# Sensor_board.net
KiCad netlist of a schematic drawn in EAGLE
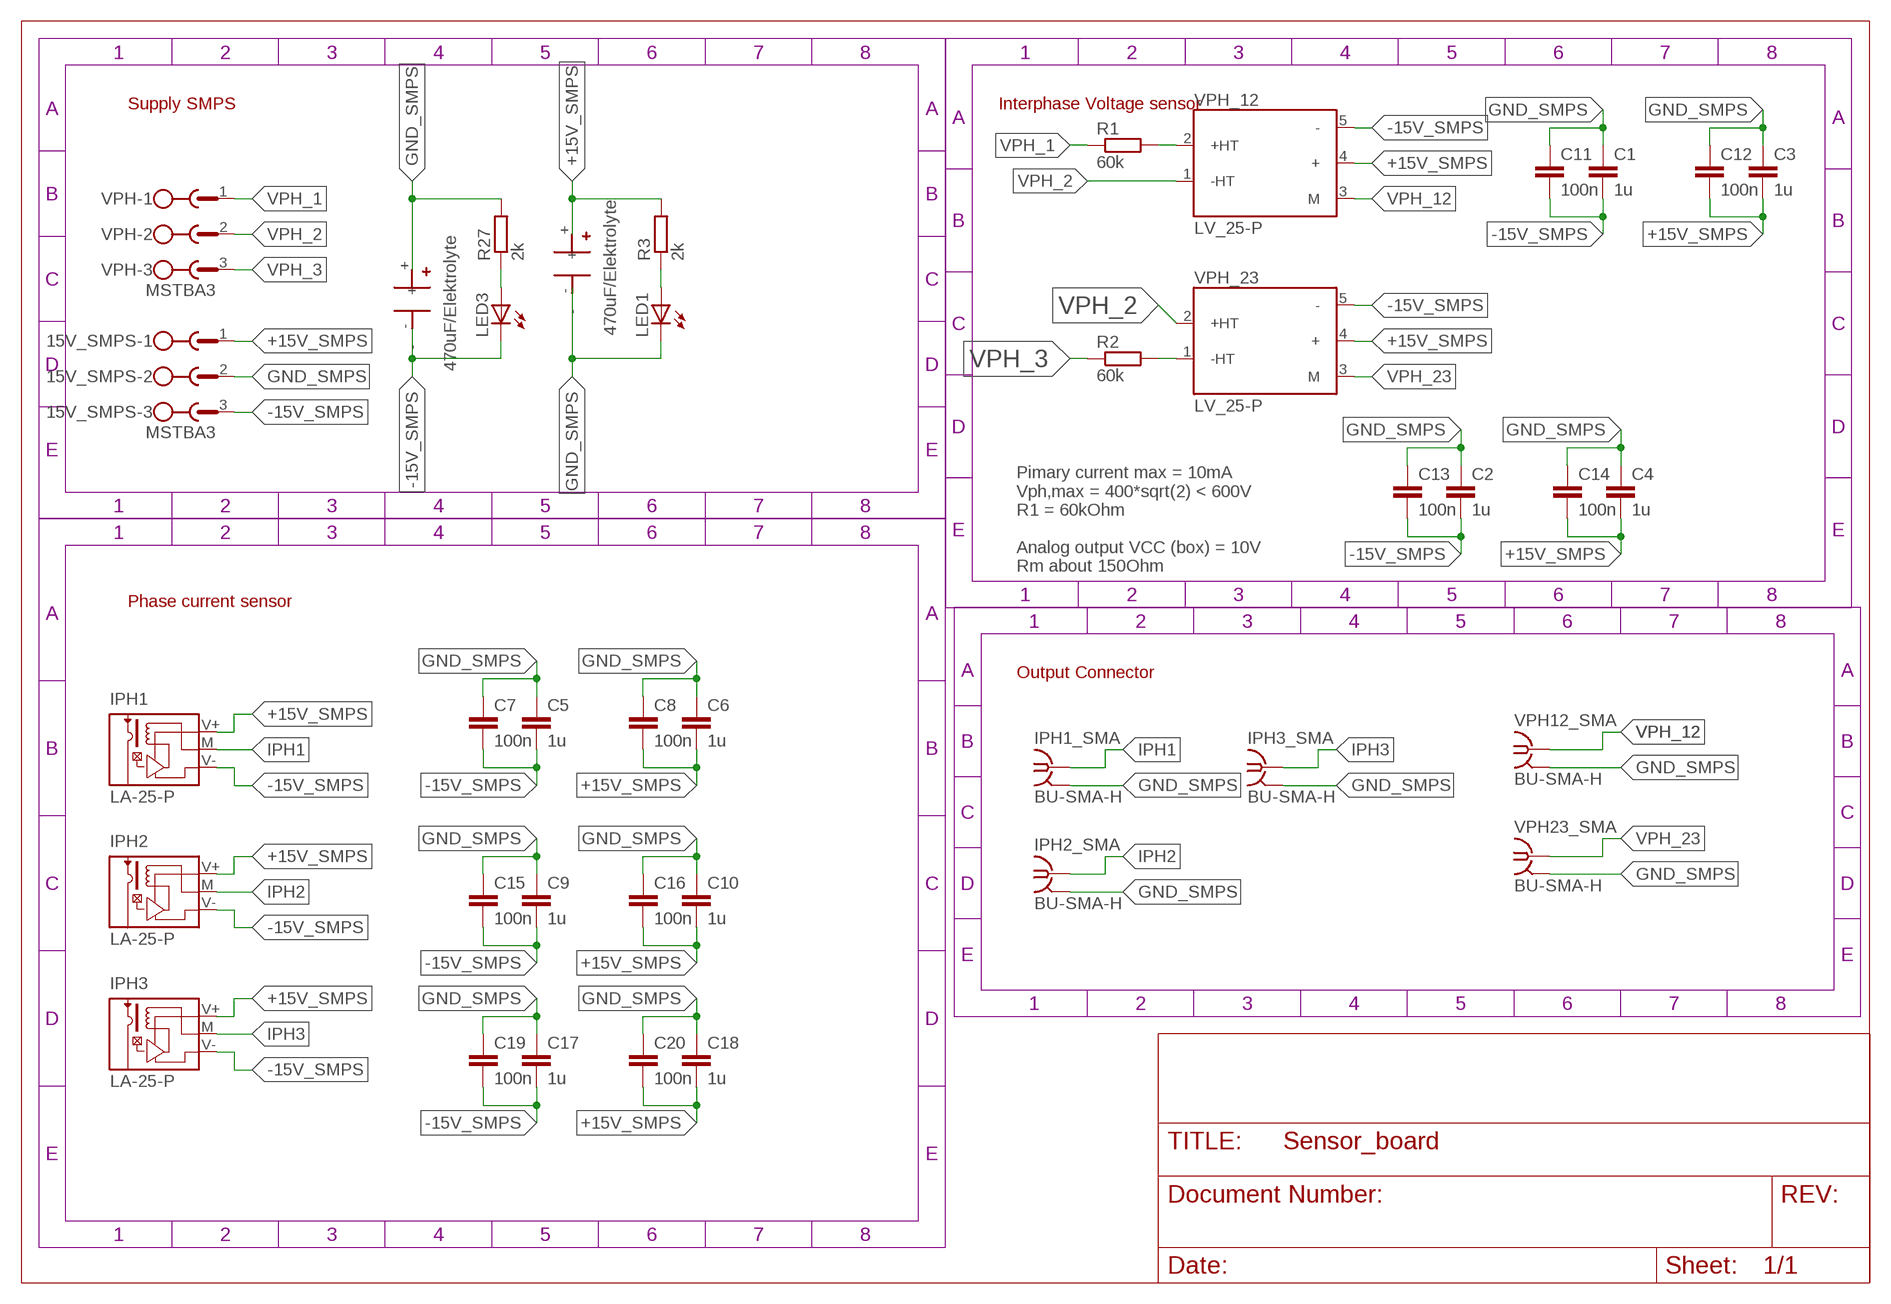
[diagram p0: schematic, sheet 1]

(export (version "E")
  (design (tool "Eeschema 10.0.6"))
  (components
    (comp (ref "15V_SMPS")
      (value "MSTBA3")
      (footprint "eagle-import:MSTBA3")
      (fields (field (name "MF") "FARNELL") (field (name "MPN") "1757255"))
      (libsource (lib "eagle-import") (part "MSTBA3"))
    )
    (comp (ref "C1")
      (value "1u")
      (footprint "eagle-import:C0805")
      (libsource (lib "eagle-import") (part "C-EUC0805"))
    )
    (comp (ref "C2")
      (value "1u")
      (footprint "eagle-import:C0805")
      (libsource (lib "eagle-import") (part "C-EUC0805"))
    )
    (comp (ref "C3")
      (value "1u")
      (footprint "eagle-import:C0805")
      (libsource (lib "eagle-import") (part "C-EUC0805"))
    )
    (comp (ref "C4")
      (value "1u")
      (footprint "eagle-import:C0805")
      (libsource (lib "eagle-import") (part "C-EUC0805"))
    )
    (comp (ref "C5")
      (value "1u")
      (footprint "eagle-import:C0805")
      (libsource (lib "eagle-import") (part "C-EUC0805"))
    )
    (comp (ref "C6")
      (value "1u")
      (footprint "eagle-import:C0805")
      (libsource (lib "eagle-import") (part "C-EUC0805"))
    )
    (comp (ref "C7")
      (value "100n")
      (footprint "eagle-import:C0805")
      (libsource (lib "eagle-import") (part "C-EUC0805"))
    )
    (comp (ref "C8")
      (value "100n")
      (footprint "eagle-import:C0805")
      (libsource (lib "eagle-import") (part "C-EUC0805"))
    )
    (comp (ref "C9")
      (value "1u")
      (footprint "eagle-import:C0805")
      (libsource (lib "eagle-import") (part "C-EUC0805"))
    )
    (comp (ref "C10")
      (value "1u")
      (footprint "eagle-import:C0805")
      (libsource (lib "eagle-import") (part "C-EUC0805"))
    )
    (comp (ref "C11")
      (value "100n")
      (footprint "eagle-import:C0805")
      (libsource (lib "eagle-import") (part "C-EUC0805"))
    )
    (comp (ref "C12")
      (value "100n")
      (footprint "eagle-import:C0805")
      (libsource (lib "eagle-import") (part "C-EUC0805"))
    )
    (comp (ref "C13")
      (value "100n")
      (footprint "eagle-import:C0805")
      (libsource (lib "eagle-import") (part "C-EUC0805"))
    )
    (comp (ref "C14")
      (value "100n")
      (footprint "eagle-import:C0805")
      (libsource (lib "eagle-import") (part "C-EUC0805"))
    )
    (comp (ref "C15")
      (value "100n")
      (footprint "eagle-import:C0805")
      (libsource (lib "eagle-import") (part "C-EUC0805"))
    )
    (comp (ref "C16")
      (value "100n")
      (footprint "eagle-import:C0805")
      (libsource (lib "eagle-import") (part "C-EUC0805"))
    )
    (comp (ref "C17")
      (value "1u")
      (footprint "eagle-import:C0805")
      (libsource (lib "eagle-import") (part "C-EUC0805"))
    )
    (comp (ref "C18")
      (value "1u")
      (footprint "eagle-import:C0805")
      (libsource (lib "eagle-import") (part "C-EUC0805"))
    )
    (comp (ref "C19")
      (value "100n")
      (footprint "eagle-import:C0805")
      (libsource (lib "eagle-import") (part "C-EUC0805"))
    )
    (comp (ref "C20")
      (value "100n")
      (footprint "eagle-import:C0805")
      (libsource (lib "eagle-import") (part "C-EUC0805"))
    )
    (comp (ref "IPH1")
      (value "LA-25-P")
      (footprint "eagle-import:LA25P")
      (libsource (lib "eagle-import") (part "LA-25-P"))
    )
    (comp (ref "IPH1_SMA")
      (value "BU-SMA-H")
      (footprint "eagle-import:BU-SMA-H")
      (libsource (lib "eagle-import") (part "BU-SMA-H"))
    )
    (comp (ref "IPH2")
      (value "LA-25-P")
      (footprint "eagle-import:LA25P")
      (libsource (lib "eagle-import") (part "LA-25-P"))
    )
    (comp (ref "IPH2_SMA")
      (value "BU-SMA-H")
      (footprint "eagle-import:BU-SMA-H")
      (libsource (lib "eagle-import") (part "BU-SMA-H"))
    )
    (comp (ref "IPH3")
      (value "LA-25-P")
      (footprint "eagle-import:LA25P")
      (libsource (lib "eagle-import") (part "LA-25-P"))
    )
    (comp (ref "IPH3_SMA")
      (value "BU-SMA-H")
      (footprint "eagle-import:BU-SMA-H")
      (libsource (lib "eagle-import") (part "BU-SMA-H"))
    )
    (comp (ref "LED1")
      (value "LEDCHIPLED_0805")
      (footprint "eagle-import:CHIPLED_0805")
      (libsource (lib "eagle-import") (part "LEDCHIPLED_0805"))
    )
    (comp (ref "LED3")
      (value "LEDCHIPLED_0805")
      (footprint "eagle-import:CHIPLED_0805")
      (libsource (lib "eagle-import") (part "LEDCHIPLED_0805"))
    )
    (comp (ref "R1")
      (value "60k")
      (footprint "eagle-import:0414_15")
      (libsource (lib "eagle-import") (part "R-EU_0414/15"))
    )
    (comp (ref "R2")
      (value "60k")
      (footprint "eagle-import:0414_15")
      (libsource (lib "eagle-import") (part "R-EU_0414/15"))
    )
    (comp (ref "R3")
      (value "2k")
      (footprint "eagle-import:R0805")
      (libsource (lib "eagle-import") (part "R-EU_R0805"))
    )
    (comp (ref "R27")
      (value "2k")
      (footprint "eagle-import:R0805")
      (libsource (lib "eagle-import") (part "R-EU_R0805"))
    )
    (comp (ref "U$1")
      (value "ELE_C_470UF_PAN")
      (footprint "eagle-import:ELEK_C_470UF_PAN")
      (libsource (lib "eagle-import") (part "ELE_C_470UF_PAN"))
    )
    (comp (ref "U$2")
      (value "ELE_C_470UF_PAN")
      (footprint "eagle-import:ELEK_C_470UF_PAN")
      (libsource (lib "eagle-import") (part "ELE_C_470UF_PAN"))
    )
    (comp (ref "VPH")
      (value "MSTBA3")
      (footprint "eagle-import:MSTBA3")
      (fields (field (name "MF") "FARNELL") (field (name "MPN") "1757255"))
      (libsource (lib "eagle-import") (part "MSTBA3"))
    )
    (comp (ref "VPH12_SMA")
      (value "BU-SMA-H")
      (footprint "eagle-import:BU-SMA-H")
      (libsource (lib "eagle-import") (part "BU-SMA-H"))
    )
    (comp (ref "VPH23_SMA")
      (value "BU-SMA-H")
      (footprint "eagle-import:BU-SMA-H")
      (libsource (lib "eagle-import") (part "BU-SMA-H"))
    )
    (comp (ref "VPH_12")
      (value "LV_25-P")
      (footprint "eagle-import:XDCR_LV25-P")
      (fields
        (field (name "DIGI-KEY_PART_NUMBER") "398-1019-ND")
        (field (name "MF") "LEM USA")
        (field (name "MP") "LV 25-P")
      )
      (libsource (lib "eagle-import") (part "LV_25-P"))
    )
    (comp (ref "VPH_23")
      (value "LV_25-P")
      (footprint "eagle-import:XDCR_LV25-P")
      (fields
        (field (name "DIGI-KEY_PART_NUMBER") "398-1019-ND")
        (field (name "MF") "LEM USA")
        (field (name "MP") "LV 25-P")
      )
      (libsource (lib "eagle-import") (part "LV_25-P"))
    )
  )
  (nets
    (net (code "1") (name "+15V_SMPS") (class "Default")
      (node (ref "15V_SMPS") (pin "1") (pinfunction "1_1") (pintype "passive"))
      (node (ref "C10") (pin "2") (pinfunction "2_2") (pintype "passive"))
      (node (ref "C12") (pin "2") (pinfunction "2_2") (pintype "passive"))
      (node (ref "C14") (pin "2") (pinfunction "2_2") (pintype "passive"))
      (node (ref "C16") (pin "2") (pinfunction "2_2") (pintype "passive"))
      (node (ref "C18") (pin "2") (pinfunction "2_2") (pintype "passive"))
      (node (ref "C20") (pin "2") (pinfunction "2_2") (pintype "passive"))
      (node (ref "C3") (pin "2") (pinfunction "2_2") (pintype "passive"))
      (node (ref "C4") (pin "2") (pinfunction "2_2") (pintype "passive"))
      (node (ref "C6") (pin "2") (pinfunction "2_2") (pintype "passive"))
      (node (ref "C8") (pin "2") (pinfunction "2_2") (pintype "passive"))
      (node (ref "IPH1") (pin "V+") (pinfunction "V+_V+") (pintype "input"))
      (node (ref "IPH2") (pin "V+") (pinfunction "V+_V+") (pintype "input"))
      (node (ref "IPH3") (pin "V+") (pinfunction "V+_V+") (pintype "input"))
      (node (ref "R3") (pin "2") (pinfunction "2_2") (pintype "passive"))
      (node (ref "U$2") (pin "+") (pinfunction "+_+") (pintype "bidirectional"))
      (node (ref "VPH_12") (pin "4") (pinfunction "+_4") (pintype "output"))
      (node (ref "VPH_23") (pin "4") (pinfunction "+_4") (pintype "output"))
    )
    (net (code "2") (name "-15V_SMPS") (class "Default")
      (node (ref "15V_SMPS") (pin "3") (pinfunction "1_3") (pintype "passive"))
      (node (ref "C1") (pin "2") (pinfunction "2_2") (pintype "passive"))
      (node (ref "C11") (pin "2") (pinfunction "2_2") (pintype "passive"))
      (node (ref "C13") (pin "2") (pinfunction "2_2") (pintype "passive"))
      (node (ref "C15") (pin "2") (pinfunction "2_2") (pintype "passive"))
      (node (ref "C17") (pin "2") (pinfunction "2_2") (pintype "passive"))
      (node (ref "C19") (pin "2") (pinfunction "2_2") (pintype "passive"))
      (node (ref "C2") (pin "2") (pinfunction "2_2") (pintype "passive"))
      (node (ref "C5") (pin "2") (pinfunction "2_2") (pintype "passive"))
      (node (ref "C7") (pin "2") (pinfunction "2_2") (pintype "passive"))
      (node (ref "C9") (pin "2") (pinfunction "2_2") (pintype "passive"))
      (node (ref "IPH1") (pin "V-") (pinfunction "V-_V-") (pintype "input"))
      (node (ref "IPH2") (pin "V-") (pinfunction "V-_V-") (pintype "input"))
      (node (ref "IPH3") (pin "V-") (pinfunction "V-_V-") (pintype "input"))
      (node (ref "LED3") (pin "C") (pinfunction "C_C") (pintype "passive"))
      (node (ref "U$1") (pin "-") (pinfunction "-_-") (pintype "bidirectional"))
      (node (ref "VPH_12") (pin "5") (pinfunction "-_5") (pintype "output"))
      (node (ref "VPH_23") (pin "5") (pinfunction "-_5") (pintype "output"))
    )
    (net (code "3") (name "GND_SMPS") (class "Default")
      (node (ref "15V_SMPS") (pin "2") (pinfunction "1_2") (pintype "passive"))
      (node (ref "C1") (pin "1") (pinfunction "1_1") (pintype "passive"))
      (node (ref "C10") (pin "1") (pinfunction "1_1") (pintype "passive"))
      (node (ref "C11") (pin "1") (pinfunction "1_1") (pintype "passive"))
      (node (ref "C12") (pin "1") (pinfunction "1_1") (pintype "passive"))
      (node (ref "C13") (pin "1") (pinfunction "1_1") (pintype "passive"))
      (node (ref "C14") (pin "1") (pinfunction "1_1") (pintype "passive"))
      (node (ref "C15") (pin "1") (pinfunction "1_1") (pintype "passive"))
      (node (ref "C16") (pin "1") (pinfunction "1_1") (pintype "passive"))
      (node (ref "C17") (pin "1") (pinfunction "1_1") (pintype "passive"))
      (node (ref "C18") (pin "1") (pinfunction "1_1") (pintype "passive"))
      (node (ref "C19") (pin "1") (pinfunction "1_1") (pintype "passive"))
      (node (ref "C2") (pin "1") (pinfunction "1_1") (pintype "passive"))
      (node (ref "C20") (pin "1") (pinfunction "1_1") (pintype "passive"))
      (node (ref "C3") (pin "1") (pinfunction "1_1") (pintype "passive"))
      (node (ref "C4") (pin "1") (pinfunction "1_1") (pintype "passive"))
      (node (ref "C5") (pin "1") (pinfunction "1_1") (pintype "passive"))
      (node (ref "C6") (pin "1") (pinfunction "1_1") (pintype "passive"))
      (node (ref "C7") (pin "1") (pinfunction "1_1") (pintype "passive"))
      (node (ref "C8") (pin "1") (pinfunction "1_1") (pintype "passive"))
      (node (ref "C9") (pin "1") (pinfunction "1_1") (pintype "passive"))
      (node (ref "IPH1_SMA") (pin "2") (pinfunction "2_2") (pintype "passive"))
      (node (ref "IPH1_SMA") (pin "3") (pinfunction "2_3") (pintype "passive"))
      (node (ref "IPH1_SMA") (pin "4") (pinfunction "2_4") (pintype "passive"))
      (node (ref "IPH1_SMA") (pin "5") (pinfunction "2_5") (pintype "passive"))
      (node (ref "IPH2_SMA") (pin "2") (pinfunction "2_2") (pintype "passive"))
      (node (ref "IPH2_SMA") (pin "3") (pinfunction "2_3") (pintype "passive"))
      (node (ref "IPH2_SMA") (pin "4") (pinfunction "2_4") (pintype "passive"))
      (node (ref "IPH2_SMA") (pin "5") (pinfunction "2_5") (pintype "passive"))
      (node (ref "IPH3_SMA") (pin "2") (pinfunction "2_2") (pintype "passive"))
      (node (ref "IPH3_SMA") (pin "3") (pinfunction "2_3") (pintype "passive"))
      (node (ref "IPH3_SMA") (pin "4") (pinfunction "2_4") (pintype "passive"))
      (node (ref "IPH3_SMA") (pin "5") (pinfunction "2_5") (pintype "passive"))
      (node (ref "LED1") (pin "C") (pinfunction "C_C") (pintype "passive"))
      (node (ref "R27") (pin "2") (pinfunction "2_2") (pintype "passive"))
      (node (ref "U$1") (pin "+") (pinfunction "+_+") (pintype "bidirectional"))
      (node (ref "U$2") (pin "-") (pinfunction "-_-") (pintype "bidirectional"))
      (node (ref "VPH12_SMA") (pin "2") (pinfunction "2_2") (pintype "passive"))
      (node (ref "VPH12_SMA") (pin "3") (pinfunction "2_3") (pintype "passive"))
      (node (ref "VPH12_SMA") (pin "4") (pinfunction "2_4") (pintype "passive"))
      (node (ref "VPH12_SMA") (pin "5") (pinfunction "2_5") (pintype "passive"))
      (node (ref "VPH23_SMA") (pin "2") (pinfunction "2_2") (pintype "passive"))
      (node (ref "VPH23_SMA") (pin "3") (pinfunction "2_3") (pintype "passive"))
      (node (ref "VPH23_SMA") (pin "4") (pinfunction "2_4") (pintype "passive"))
      (node (ref "VPH23_SMA") (pin "5") (pinfunction "2_5") (pintype "passive"))
    )
    (net (code "4") (name "IPH1") (class "Default")
      (node (ref "IPH1") (pin "M") (pinfunction "M_M") (pintype "output"))
      (node (ref "IPH1_SMA") (pin "1") (pinfunction "1_1") (pintype "passive"))
    )
    (net (code "5") (name "IPH2") (class "Default")
      (node (ref "IPH2") (pin "M") (pinfunction "M_M") (pintype "output"))
      (node (ref "IPH2_SMA") (pin "1") (pinfunction "1_1") (pintype "passive"))
    )
    (net (code "6") (name "IPH3") (class "Default")
      (node (ref "IPH3") (pin "M") (pinfunction "M_M") (pintype "output"))
      (node (ref "IPH3_SMA") (pin "1") (pinfunction "1_1") (pintype "passive"))
    )
    (net (code "7") (name "Net-(LED1-PadA)") (class "Default")
      (node (ref "LED1") (pin "A") (pinfunction "A_A") (pintype "passive"))
      (node (ref "R3") (pin "1") (pinfunction "1_1") (pintype "passive"))
    )
    (net (code "8") (name "Net-(LED3-PadA)") (class "Default")
      (node (ref "LED3") (pin "A") (pinfunction "A_A") (pintype "passive"))
      (node (ref "R27") (pin "1") (pinfunction "1_1") (pintype "passive"))
    )
    (net (code "9") (name "Net-(VPH_12-+HT)") (class "Default")
      (node (ref "R1") (pin "2") (pinfunction "2_2") (pintype "passive"))
      (node (ref "VPH_12") (pin "2") (pinfunction "+HT_2") (pintype "input"))
    )
    (net (code "10") (name "Net-(VPH_23--HT)") (class "Default")
      (node (ref "R2") (pin "2") (pinfunction "2_2") (pintype "passive"))
      (node (ref "VPH_23") (pin "1") (pinfunction "-HT_1") (pintype "input"))
    )
    (net (code "11") (name "VPH_1") (class "Default")
      (node (ref "R1") (pin "1") (pinfunction "1_1") (pintype "passive"))
      (node (ref "VPH") (pin "1") (pinfunction "1_1") (pintype "passive"))
    )
    (net (code "12") (name "VPH_2") (class "Default")
      (node (ref "VPH") (pin "2") (pinfunction "1_2") (pintype "passive"))
      (node (ref "VPH_12") (pin "1") (pinfunction "-HT_1") (pintype "input"))
      (node (ref "VPH_23") (pin "2") (pinfunction "+HT_2") (pintype "input"))
    )
    (net (code "13") (name "VPH_3") (class "Default")
      (node (ref "R2") (pin "1") (pinfunction "1_1") (pintype "passive"))
      (node (ref "VPH") (pin "3") (pinfunction "1_3") (pintype "passive"))
    )
    (net (code "14") (name "VPH_12") (class "Default")
      (node (ref "VPH12_SMA") (pin "1") (pinfunction "1_1") (pintype "passive"))
      (node (ref "VPH_12") (pin "3") (pinfunction "M_3") (pintype "output"))
    )
    (net (code "15") (name "VPH_23") (class "Default")
      (node (ref "VPH23_SMA") (pin "1") (pinfunction "1_1") (pintype "passive"))
      (node (ref "VPH_23") (pin "3") (pinfunction "M_3") (pintype "output"))
    )
  )
)
